# big_8x16.net
KiCad netlist of a schematic drawn in EAGLE
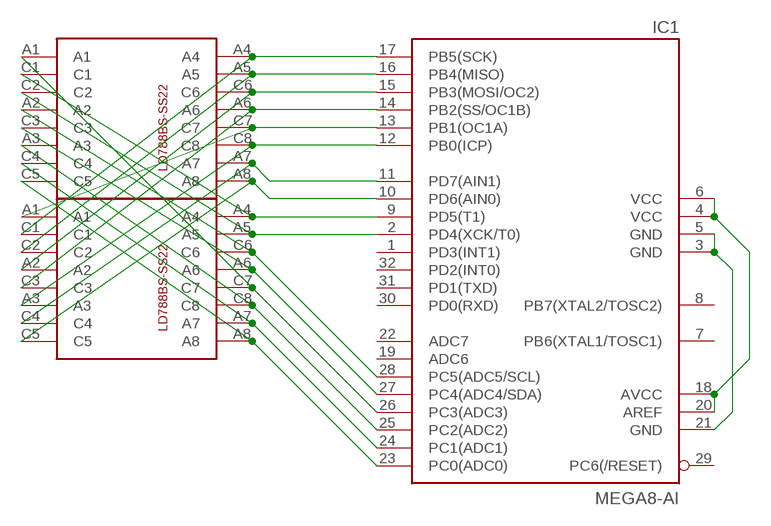
[diagram p0: schematic, sheet 1]

(export (version "E")
  (design (tool "Eeschema 10.0.6"))
  (components
    (comp (ref "IC1")
      (value "MEGA8-AI")
      (footprint "eagle-import:TQFP32-08")
      (fields (field (name "MPN") "ATMEGA8-16AU"))
      (libsource (lib "eagle-import") (part "MEGA8-AI"))
    )
    (comp (ref "U$1")
      (value "LD-1088BS")
      (footprint "eagle-import:LD-1088BS")
      (libsource (lib "eagle-import") (part "LD-1088BS"))
    )
    (comp (ref "U$2")
      (value "LD-1088BS")
      (footprint "eagle-import:LD-1088BS")
      (libsource (lib "eagle-import") (part "LD-1088BS"))
    )
  )
  (nets
    (net (code "1") (name "Net-(IC1-AREF)") (class "Default")
      (node (ref "IC1") (pin "18") (pinfunction "AVCC_18") (pintype "power_in"))
      (node (ref "IC1") (pin "20") (pinfunction "AREF_20") (pintype "passive"))
      (node (ref "IC1") (pin "4") (pinfunction "VCC_4") (pintype "power_in"))
      (node (ref "IC1") (pin "6") (pinfunction "VCC_6") (pintype "power_in"))
    )
    (net (code "2") (name "Net-(IC1-GND-Pad21)") (class "Default")
      (node (ref "IC1") (pin "21") (pinfunction "GND_21") (pintype "power_in"))
      (node (ref "IC1") (pin "3") (pinfunction "GND_3") (pintype "power_in"))
      (node (ref "IC1") (pin "5") (pinfunction "GND_5") (pintype "power_in"))
    )
    (net (code "3") (name "Net-(IC1-PB0(ICP))") (class "Default")
      (node (ref "IC1") (pin "12") (pinfunction "PB0(ICP)_12") (pintype "bidirectional"))
      (node (ref "U$1") (pin "A3") (pinfunction "A3_A3") (pintype "bidirectional"))
      (node (ref "U$2") (pin "C8") (pinfunction "C8_C8") (pintype "bidirectional"))
    )
    (net (code "4") (name "Net-(IC1-PB1(OC1A))") (class "Default")
      (node (ref "IC1") (pin "13") (pinfunction "PB1(OC1A)_13") (pintype "bidirectional"))
      (node (ref "U$1") (pin "A1") (pinfunction "A1_A1") (pintype "bidirectional"))
      (node (ref "U$2") (pin "C7") (pinfunction "C7_C7") (pintype "bidirectional"))
    )
    (net (code "5") (name "Net-(IC1-PB2(SS{slash}OC1B))") (class "Default")
      (node (ref "IC1") (pin "14") (pinfunction "PB2(SS/OC1B)_14") (pintype "bidirectional"))
      (node (ref "U$1") (pin "C3") (pinfunction "C3_C3") (pintype "bidirectional"))
      (node (ref "U$2") (pin "A6") (pinfunction "A6_A6") (pintype "bidirectional"))
    )
    (net (code "6") (name "Net-(IC1-PB3(MOSI{slash}OC2))") (class "Default")
      (node (ref "IC1") (pin "15") (pinfunction "PB3(MOSI/OC2)_15") (pintype "bidirectional"))
      (node (ref "U$1") (pin "A2") (pinfunction "A2_A2") (pintype "bidirectional"))
      (node (ref "U$2") (pin "C6") (pinfunction "C6_C6") (pintype "bidirectional"))
    )
    (net (code "7") (name "Net-(IC1-PB4(MISO))") (class "Default")
      (node (ref "IC1") (pin "16") (pinfunction "PB4(MISO)_16") (pintype "bidirectional"))
      (node (ref "U$1") (pin "C2") (pinfunction "C2_C2") (pintype "bidirectional"))
      (node (ref "U$2") (pin "A5") (pinfunction "A5_A5") (pintype "bidirectional"))
    )
    (net (code "8") (name "Net-(IC1-PB5(SCK))") (class "Default")
      (node (ref "IC1") (pin "17") (pinfunction "PB5(SCK)_17") (pintype "bidirectional"))
      (node (ref "U$1") (pin "C1") (pinfunction "C1_C1") (pintype "bidirectional"))
      (node (ref "U$2") (pin "A4") (pinfunction "A4_A4") (pintype "bidirectional"))
    )
    (net (code "9") (name "Net-(IC1-PC0(ADC0))") (class "Default")
      (node (ref "IC1") (pin "23") (pinfunction "PC0(ADC0)_23") (pintype "bidirectional"))
      (node (ref "U$1") (pin "A8") (pinfunction "A8_A8") (pintype "bidirectional"))
      (node (ref "U$2") (pin "C5") (pinfunction "C5_C5") (pintype "bidirectional"))
    )
    (net (code "10") (name "Net-(IC1-PC1(ADC1))") (class "Default")
      (node (ref "IC1") (pin "24") (pinfunction "PC1(ADC1)_24") (pintype "bidirectional"))
      (node (ref "U$1") (pin "A7") (pinfunction "A7_A7") (pintype "bidirectional"))
      (node (ref "U$2") (pin "C4") (pinfunction "C4_C4") (pintype "bidirectional"))
    )
    (net (code "11") (name "Net-(IC1-PC2(ADC2))") (class "Default")
      (node (ref "IC1") (pin "25") (pinfunction "PC2(ADC2)_25") (pintype "bidirectional"))
      (node (ref "U$1") (pin "C8") (pinfunction "C8_C8") (pintype "bidirectional"))
      (node (ref "U$2") (pin "A3") (pinfunction "A3_A3") (pintype "bidirectional"))
    )
    (net (code "12") (name "Net-(IC1-PC3(ADC3))") (class "Default")
      (node (ref "IC1") (pin "26") (pinfunction "PC3(ADC3)_26") (pintype "bidirectional"))
      (node (ref "U$1") (pin "C7") (pinfunction "C7_C7") (pintype "bidirectional"))
      (node (ref "U$2") (pin "A1") (pinfunction "A1_A1") (pintype "bidirectional"))
    )
    (net (code "13") (name "Net-(IC1-PC4(ADC4{slash}SDA))") (class "Default")
      (node (ref "IC1") (pin "27") (pinfunction "PC4(ADC4/SDA)_27") (pintype "bidirectional"))
      (node (ref "U$1") (pin "A6") (pinfunction "A6_A6") (pintype "bidirectional"))
      (node (ref "U$2") (pin "C3") (pinfunction "C3_C3") (pintype "bidirectional"))
    )
    (net (code "14") (name "Net-(IC1-PC5(ADC5{slash}SCL))") (class "Default")
      (node (ref "IC1") (pin "28") (pinfunction "PC5(ADC5/SCL)_28") (pintype "bidirectional"))
      (node (ref "U$1") (pin "C6") (pinfunction "C6_C6") (pintype "bidirectional"))
      (node (ref "U$2") (pin "A2") (pinfunction "A2_A2") (pintype "bidirectional"))
    )
    (net (code "15") (name "Net-(IC1-PD4(XCK{slash}T0))") (class "Default")
      (node (ref "IC1") (pin "2") (pinfunction "PD4(XCK/T0)_2") (pintype "bidirectional"))
      (node (ref "U$1") (pin "A5") (pinfunction "A5_A5") (pintype "bidirectional"))
      (node (ref "U$2") (pin "C2") (pinfunction "C2_C2") (pintype "bidirectional"))
    )
    (net (code "16") (name "Net-(IC1-PD5(T1))") (class "Default")
      (node (ref "IC1") (pin "9") (pinfunction "PD5(T1)_9") (pintype "bidirectional"))
      (node (ref "U$1") (pin "A4") (pinfunction "A4_A4") (pintype "bidirectional"))
      (node (ref "U$2") (pin "C1") (pinfunction "C1_C1") (pintype "bidirectional"))
    )
    (net (code "17") (name "Net-(IC1-PD6(AIN0))") (class "Default")
      (node (ref "IC1") (pin "10") (pinfunction "PD6(AIN0)_10") (pintype "bidirectional"))
      (node (ref "U$1") (pin "C5") (pinfunction "C5_C5") (pintype "bidirectional"))
      (node (ref "U$2") (pin "A8") (pinfunction "A8_A8") (pintype "bidirectional"))
    )
    (net (code "18") (name "Net-(IC1-PD7(AIN1))") (class "Default")
      (node (ref "IC1") (pin "11") (pinfunction "PD7(AIN1)_11") (pintype "bidirectional"))
      (node (ref "U$1") (pin "C4") (pinfunction "C4_C4") (pintype "bidirectional"))
      (node (ref "U$2") (pin "A7") (pinfunction "A7_A7") (pintype "bidirectional"))
    )
    (net (code "19") (name "unconnected-(IC1-ADC6-Pad19)") (class "Default")
      (node (ref "IC1") (pin "19") (pinfunction "ADC6_19") (pintype "bidirectional"))
    )
    (net (code "20") (name "unconnected-(IC1-ADC7-Pad22)") (class "Default")
      (node (ref "IC1") (pin "22") (pinfunction "ADC7_22") (pintype "bidirectional"))
    )
    (net (code "21") (name "unconnected-(IC1-PB6(XTAL1{slash}TOSC1)-Pad7)") (class "Default")
      (node (ref "IC1") (pin "7") (pinfunction "PB6(XTAL1/TOSC1)_7") (pintype "bidirectional"))
    )
    (net (code "22") (name "unconnected-(IC1-PB7(XTAL2{slash}TOSC2)-Pad8)") (class "Default")
      (node (ref "IC1") (pin "8") (pinfunction "PB7(XTAL2/TOSC2)_8") (pintype "bidirectional"))
    )
    (net (code "23") (name "unconnected-(IC1-PC6({slash}RESET)-Pad29)") (class "Default")
      (node (ref "IC1") (pin "29") (pinfunction "PC6(/RESET)_29") (pintype "bidirectional"))
    )
    (net (code "24") (name "unconnected-(IC1-PD0(RXD)-Pad30)") (class "Default")
      (node (ref "IC1") (pin "30") (pinfunction "PD0(RXD)_30") (pintype "bidirectional"))
    )
    (net (code "25") (name "unconnected-(IC1-PD1(TXD)-Pad31)") (class "Default")
      (node (ref "IC1") (pin "31") (pinfunction "PD1(TXD)_31") (pintype "bidirectional"))
    )
    (net (code "26") (name "unconnected-(IC1-PD2(INT0)-Pad32)") (class "Default")
      (node (ref "IC1") (pin "32") (pinfunction "PD2(INT0)_32") (pintype "bidirectional"))
    )
    (net (code "27") (name "unconnected-(IC1-PD3(INT1)-Pad1)") (class "Default")
      (node (ref "IC1") (pin "1") (pinfunction "PD3(INT1)_1") (pintype "bidirectional"))
    )
  )
)
